# pcb_gift.net
KiCad netlist of a schematic drawn in EAGLE
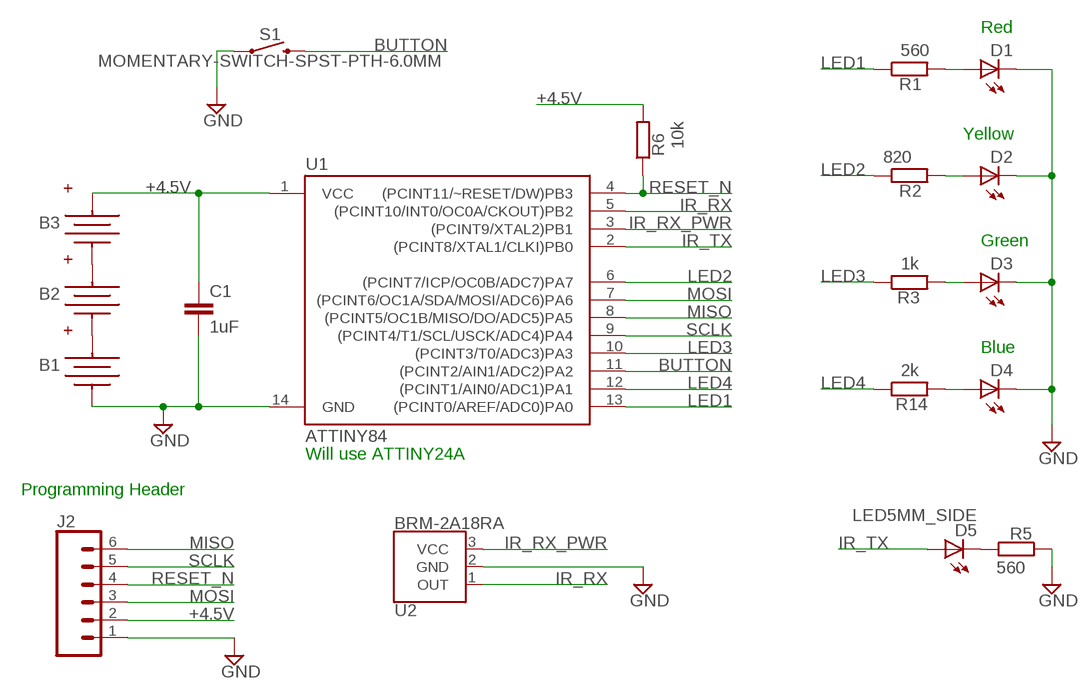
[diagram p0: schematic, sheet 1]

(export (version "E")
  (design (tool "Eeschema 10.0.6"))
  (components
    (comp (ref "B1")
      (value "KEYSTONE_2996")
      (footprint "eagle-import:KEYSTONE_2996")
      (libsource (lib "eagle-import") (part "KEYSTONE_2996"))
    )
    (comp (ref "B2")
      (value "KEYSTONE_2996")
      (footprint "eagle-import:KEYSTONE_2996")
      (libsource (lib "eagle-import") (part "KEYSTONE_2996"))
    )
    (comp (ref "B3")
      (value "KEYSTONE_2996")
      (footprint "eagle-import:KEYSTONE_2996")
      (libsource (lib "eagle-import") (part "KEYSTONE_2996"))
    )
    (comp (ref "C1")
      (value "1uF")
      (footprint "eagle-import:C0805")
      (libsource (lib "eagle-import") (part "C-EUC0805"))
    )
    (comp (ref "D1")
      (value "LED5MM")
      (footprint "eagle-import:LED5MM")
      (libsource (lib "eagle-import") (part "LED5MM"))
    )
    (comp (ref "D2")
      (value "LED5MM")
      (footprint "eagle-import:LED5MM")
      (libsource (lib "eagle-import") (part "LED5MM"))
    )
    (comp (ref "D3")
      (value "LED5MM")
      (footprint "eagle-import:LED5MM")
      (libsource (lib "eagle-import") (part "LED5MM"))
    )
    (comp (ref "D4")
      (value "LED5MM")
      (footprint "eagle-import:LED5MM")
      (libsource (lib "eagle-import") (part "LED5MM"))
    )
    (comp (ref "D5")
      (value "LED5MM_SIDE")
      (footprint "eagle-import:LED5MM_SIDE")
      (libsource (lib "eagle-import") (part "LED5MM_SIDE"))
    )
    (comp (ref "J2")
      (value "CONN_061.27MM")
      (footprint "eagle-import:1X06_1.27MM")
      (libsource (lib "eagle-import") (part "CONN_061.27MM"))
    )
    (comp (ref "R1")
      (value "560")
      (footprint "eagle-import:R0805")
      (libsource (lib "eagle-import") (part "R-EU_R0805"))
    )
    (comp (ref "R2")
      (value "820")
      (footprint "eagle-import:R0805")
      (libsource (lib "eagle-import") (part "R-EU_R0805"))
    )
    (comp (ref "R3")
      (value "1k")
      (footprint "eagle-import:R0805")
      (libsource (lib "eagle-import") (part "R-EU_R0805"))
    )
    (comp (ref "R5")
      (value "560")
      (footprint "eagle-import:R0805")
      (libsource (lib "eagle-import") (part "R-EU_R0805"))
    )
    (comp (ref "R6")
      (value "10k")
      (footprint "eagle-import:R0805")
      (libsource (lib "eagle-import") (part "R-EU_R0805"))
    )
    (comp (ref "R14")
      (value "2k")
      (footprint "eagle-import:R0805")
      (libsource (lib "eagle-import") (part "R-EU_R0805"))
    )
    (comp (ref "S1")
      (value "MOMENTARY-SWITCH-SPST-PTH-6.0MM")
      (footprint "eagle-import:TACTILE_SWITCH_PTH_6.0MM")
      (libsource (lib "eagle-import") (part "MOMENTARY-SWITCH-SPST-PTH-6.0MM"))
    )
    (comp (ref "U1")
      (value "ATTINY84")
      (footprint "eagle-import:SO14")
      (libsource (lib "eagle-import") (part "ATTINY84"))
    )
    (comp (ref "U2")
      (value "BRM-2A18RA")
      (footprint "eagle-import:BRM-2508")
      (libsource (lib "eagle-import") (part "BRM-2A18RA"))
    )
  )
  (nets
    (net (code "1") (name "/+4.5V") (class "Default")
      (node (ref "B3") (pin "POSA") (pinfunction "POS_POSA") (pintype "bidirectional"))
      (node (ref "B3") (pin "POSB") (pinfunction "POS_POSB") (pintype "bidirectional"))
      (node (ref "C1") (pin "1") (pinfunction "1_1") (pintype "passive"))
      (node (ref "J2") (pin "2") (pinfunction "2_2") (pintype "passive"))
      (node (ref "R6") (pin "2") (pinfunction "2_2") (pintype "passive"))
      (node (ref "U1") (pin "1") (pinfunction "VCC_1") (pintype "bidirectional"))
    )
    (net (code "2") (name "/BUTTON") (class "Default")
      (node (ref "S1") (pin "3") (pinfunction "2_3") (pintype "passive"))
      (node (ref "U1") (pin "11") (pinfunction "(PCINT2/AIN1/ADC2)PA2_11") (pintype "bidirectional"))
    )
    (net (code "3") (name "/IR_RX") (class "Default")
      (node (ref "U1") (pin "5") (pinfunction "(PCINT10/INT0/OC0A/CKOUT)PB2_5") (pintype "bidirectional"))
      (node (ref "U2") (pin "1") (pinfunction "OUT_1") (pintype "bidirectional"))
    )
    (net (code "4") (name "/IR_RX_PWR") (class "Default")
      (node (ref "U1") (pin "3") (pinfunction "(PCINT9/XTAL2)PB1_3") (pintype "bidirectional"))
      (node (ref "U2") (pin "3") (pinfunction "VCC_3") (pintype "bidirectional"))
    )
    (net (code "5") (name "/IR_TX") (class "Default")
      (node (ref "D5") (pin "A") (pinfunction "A_A") (pintype "passive"))
      (node (ref "U1") (pin "2") (pinfunction "(PCINT8/XTAL1/CLKI)PB0_2") (pintype "bidirectional"))
    )
    (net (code "6") (name "/LED1") (class "Default")
      (node (ref "R1") (pin "1") (pinfunction "1_1") (pintype "passive"))
      (node (ref "U1") (pin "13") (pinfunction "(PCINT0/AREF/ADC0)PA0_13") (pintype "bidirectional"))
    )
    (net (code "7") (name "/LED2") (class "Default")
      (node (ref "R2") (pin "1") (pinfunction "1_1") (pintype "passive"))
      (node (ref "U1") (pin "6") (pinfunction "(PCINT7/ICP/OC0B/ADC7)PA7_6") (pintype "bidirectional"))
    )
    (net (code "8") (name "/LED3") (class "Default")
      (node (ref "R3") (pin "1") (pinfunction "1_1") (pintype "passive"))
      (node (ref "U1") (pin "10") (pinfunction "(PCINT3/T0/ADC3)PA3_10") (pintype "bidirectional"))
    )
    (net (code "9") (name "/LED4") (class "Default")
      (node (ref "R14") (pin "1") (pinfunction "1_1") (pintype "passive"))
      (node (ref "U1") (pin "12") (pinfunction "(PCINT1/AIN0/ADC1)PA1_12") (pintype "bidirectional"))
    )
    (net (code "10") (name "/MISO") (class "Default")
      (node (ref "J2") (pin "6") (pinfunction "6_6") (pintype "passive"))
      (node (ref "U1") (pin "8") (pinfunction "(PCINT5/OC1B/MISO/DO/ADC5)PA5_8") (pintype "bidirectional"))
    )
    (net (code "11") (name "/MOSI") (class "Default")
      (node (ref "J2") (pin "3") (pinfunction "3_3") (pintype "passive"))
      (node (ref "U1") (pin "7") (pinfunction "(PCINT6/OC1A/SDA/MOSI/ADC6)PA6_7") (pintype "bidirectional"))
    )
    (net (code "12") (name "/RESET_N") (class "Default")
      (node (ref "J2") (pin "4") (pinfunction "4_4") (pintype "passive"))
      (node (ref "R6") (pin "1") (pinfunction "1_1") (pintype "passive"))
      (node (ref "U1") (pin "4") (pinfunction "(PCINT11/~{RESET/DW})PB3_4") (pintype "bidirectional"))
    )
    (net (code "13") (name "/SCLK") (class "Default")
      (node (ref "J2") (pin "5") (pinfunction "5_5") (pintype "passive"))
      (node (ref "U1") (pin "9") (pinfunction "(PCINT4/T1/SCL/USCK/ADC4)PA4_9") (pintype "bidirectional"))
    )
    (net (code "14") (name "GND") (class "Default")
      (node (ref "B1") (pin "NEG") (pinfunction "NEG_NEG") (pintype "bidirectional"))
      (node (ref "C1") (pin "2") (pinfunction "2_2") (pintype "passive"))
      (node (ref "D1") (pin "K") (pinfunction "C_K") (pintype "passive"))
      (node (ref "D2") (pin "K") (pinfunction "C_K") (pintype "passive"))
      (node (ref "D3") (pin "K") (pinfunction "C_K") (pintype "passive"))
      (node (ref "D4") (pin "K") (pinfunction "C_K") (pintype "passive"))
      (node (ref "J2") (pin "1") (pinfunction "1_1") (pintype "passive"))
      (node (ref "R5") (pin "1") (pinfunction "1_1") (pintype "passive"))
      (node (ref "S1") (pin "1") (pinfunction "1_1") (pintype "passive"))
      (node (ref "U1") (pin "14") (pinfunction "GND_14") (pintype "bidirectional"))
      (node (ref "U2") (pin "2") (pinfunction "GND_2") (pintype "bidirectional"))
    )
    (net (code "15") (name "Net-(B1-POS-PadPOSA)") (class "Default")
      (node (ref "B1") (pin "POSA") (pinfunction "POS_POSA") (pintype "bidirectional"))
      (node (ref "B1") (pin "POSB") (pinfunction "POS_POSB") (pintype "bidirectional"))
      (node (ref "B2") (pin "NEG") (pinfunction "NEG_NEG") (pintype "bidirectional"))
    )
    (net (code "16") (name "Net-(B2-POS-PadPOSA)") (class "Default")
      (node (ref "B2") (pin "POSA") (pinfunction "POS_POSA") (pintype "bidirectional"))
      (node (ref "B2") (pin "POSB") (pinfunction "POS_POSB") (pintype "bidirectional"))
      (node (ref "B3") (pin "NEG") (pinfunction "NEG_NEG") (pintype "bidirectional"))
    )
    (net (code "17") (name "Net-(D1-PadA)") (class "Default")
      (node (ref "D1") (pin "A") (pinfunction "A_A") (pintype "passive"))
      (node (ref "R1") (pin "2") (pinfunction "2_2") (pintype "passive"))
    )
    (net (code "18") (name "Net-(D2-PadA)") (class "Default")
      (node (ref "D2") (pin "A") (pinfunction "A_A") (pintype "passive"))
      (node (ref "R2") (pin "2") (pinfunction "2_2") (pintype "passive"))
    )
    (net (code "19") (name "Net-(D3-PadA)") (class "Default")
      (node (ref "D3") (pin "A") (pinfunction "A_A") (pintype "passive"))
      (node (ref "R3") (pin "2") (pinfunction "2_2") (pintype "passive"))
    )
    (net (code "20") (name "Net-(D4-PadA)") (class "Default")
      (node (ref "D4") (pin "A") (pinfunction "A_A") (pintype "passive"))
      (node (ref "R14") (pin "2") (pinfunction "2_2") (pintype "passive"))
    )
    (net (code "21") (name "Net-(D5-C)") (class "Default")
      (node (ref "D5") (pin "K") (pinfunction "C_K") (pintype "passive"))
      (node (ref "R5") (pin "2") (pinfunction "2_2") (pintype "passive"))
    )
  )
)
